# Charger.net
KiCad netlist of a schematic drawn in Altium Designer
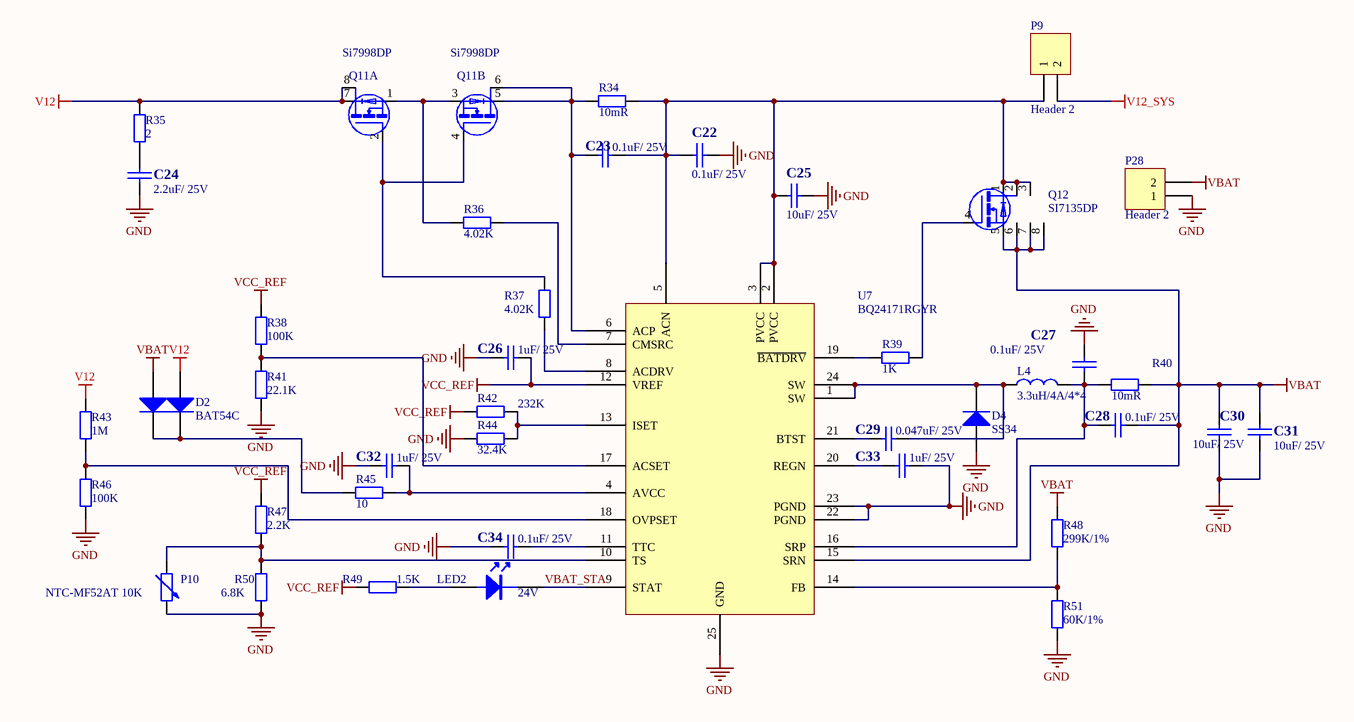
[diagram p0: Charger.SchDoc]

(export (version "E")
  (design (tool "Eeschema 10.0.6"))
  (components
    (comp (ref "C22")
      (value "0.1uF/ 25V")
      (footprint "0603C")
      (description "Capacitor")
      (libsource (lib "*") (part "CAP"))
    )
    (comp (ref "C23")
      (value "0.1uF/ 25V")
      (footprint "0603C")
      (description "Capacitor")
      (libsource (lib "*") (part "CAP"))
    )
    (comp (ref "C24")
      (value "2.2uF/ 25V")
      (footprint "0603C")
      (description "Capacitor")
      (libsource (lib "*") (part "CAP"))
    )
    (comp (ref "C25")
      (value "10uF/ 25V")
      (footprint "0603C")
      (description "Capacitor")
      (libsource (lib "*") (part "CAP"))
    )
    (comp (ref "C26")
      (value "1uF/ 25V")
      (footprint "0603C")
      (description "Capacitor")
      (libsource (lib "*") (part "CAP"))
    )
    (comp (ref "C27")
      (value "0.1uF/ 25V")
      (footprint "0603C")
      (description "Capacitor")
      (libsource (lib "*") (part "CAP"))
    )
    (comp (ref "C28")
      (value "0.1uF/ 25V")
      (footprint "0603C")
      (description "Capacitor")
      (libsource (lib "*") (part "CAP"))
    )
    (comp (ref "C29")
      (value "0.047uF/ 25V")
      (footprint "0603C")
      (description "Capacitor")
      (libsource (lib "*") (part "CAP"))
    )
    (comp (ref "C30")
      (value "10uF/ 25V")
      (footprint "0603C")
      (description "Capacitor")
      (libsource (lib "*") (part "CAP"))
    )
    (comp (ref "C31")
      (value "10uF/ 25V")
      (footprint "0603C")
      (description "Capacitor")
      (libsource (lib "*") (part "CAP"))
    )
    (comp (ref "C32")
      (value "1uF/ 25V")
      (footprint "0603C")
      (description "Capacitor")
      (libsource (lib "*") (part "CAP"))
    )
    (comp (ref "C33")
      (value "1uF/ 25V")
      (footprint "0603C")
      (description "Capacitor")
      (libsource (lib "*") (part "CAP"))
    )
    (comp (ref "C34")
      (value "0.1uF/ 25V")
      (footprint "0603C")
      (description "Capacitor")
      (libsource (lib "*") (part "CAP"))
    )
    (comp (ref "D2") (value "BAT54C") (footprint "SOT23-3") (libsource (lib "stm32") (part "BAT54C")))
    (comp (ref "D4") (value "SS34") (footprint "SMA") (libsource (lib "Sch_library") (part "DIODE")))
    (comp (ref "L4")
      (value "3.3uH/4A/4*4")
      (footprint "INDUCTOR_4X4X2")
      (libsource (lib "Sch_library") (part "IND"))
    )
    (comp (ref "LED2") (value "24V") (footprint "0603LED") (libsource (lib "*") (part "LED")))
    (comp (ref "P9")
      (value "Header 2")
      (footprint "HDR1X2")
      (description "Header, 2-Pin")
      (fields (field (name "PUBLISHER") "Altium Limited"))
      (libsource (lib "Miscellaneous Connectors") (part "Header 2"))
    )
    (comp (ref "P10")
      (value "NTC-MF52AT 10K")
      (footprint "SMD-0603")
      (description "卧贴")
      (libsource (lib "ABB") (part "RES3"))
    )
    (comp (ref "P28")
      (value "Header 2")
      (footprint "2X2.54MMW")
      (description "Header, 2-Pin")
      (fields (field (name "PUBLISHER") "Altium Limited"))
      (libsource (lib "") (part "Header 2_1"))
    )
    (comp (ref "Q11")
      (value "Si7998DP")
      (footprint "Si7998DP")
      (libsource (lib "Y0801_V14") (part "SI7940DP"))
    )
    (comp (ref "Q12")
      (value "SI7135DP")
      (footprint "PowerPAK SO-8")
      (libsource (lib "stm32") (part "SI7135DP"))
    )
    (comp (ref "R34")
      (value "10mR")
      (footprint "2512R")
      (description "贴片电阻 5%")
      (libsource (lib "XiaoyI") (part "RES2"))
    )
    (comp (ref "R35")
      (value "2")
      (footprint "SMD-0603")
      (description "贴片电阻 5%")
      (libsource (lib "") (part "RES2_2"))
    )
    (comp (ref "R36")
      (value "4.02K")
      (footprint "SMD-0603")
      (description "贴片电阻 5%")
      (libsource (lib "XiaoyI") (part "RES2"))
    )
    (comp (ref "R37")
      (value "4.02K")
      (footprint "SMD-0603")
      (description "贴片电阻 5%")
      (libsource (lib "") (part "RES2_2"))
    )
    (comp (ref "R38")
      (value "100K")
      (footprint "SMD-0603")
      (description "贴片电阻 5%")
      (libsource (lib "") (part "RES2_2"))
    )
    (comp (ref "R39")
      (value "1K")
      (footprint "0603R")
      (description "贴片电阻 5%")
      (libsource (lib "XiaoyI") (part "RES2"))
    )
    (comp (ref "R40")
      (value "10mR")
      (footprint "2512R")
      (description "贴片电阻 5%")
      (libsource (lib "XiaoyI") (part "RES2"))
    )
    (comp (ref "R41")
      (value "22.1K")
      (footprint "SMD-0603")
      (description "贴片电阻 5%")
      (libsource (lib "") (part "RES2_2"))
    )
    (comp (ref "R42")
      (value "232K")
      (footprint "SMD-0603")
      (description "贴片电阻 5%")
      (libsource (lib "XiaoyI") (part "RES2"))
    )
    (comp (ref "R43")
      (value "1M")
      (footprint "SMD-0603")
      (description "贴片电阻 5%")
      (libsource (lib "") (part "RES2_2"))
    )
    (comp (ref "R44")
      (value "32.4K")
      (footprint "SMD-0603")
      (description "贴片电阻 5%")
      (libsource (lib "XiaoyI") (part "RES2"))
    )
    (comp (ref "R45")
      (value "10")
      (footprint "SMD-0603")
      (description "贴片电阻 5%")
      (libsource (lib "XiaoyI") (part "RES2"))
    )
    (comp (ref "R46")
      (value "100K")
      (footprint "SMD-0603")
      (description "贴片电阻 5%")
      (libsource (lib "") (part "RES2_2"))
    )
    (comp (ref "R47")
      (value "2.2K")
      (footprint "SMD-0603")
      (description "贴片电阻 5%")
      (libsource (lib "") (part "RES2_2"))
    )
    (comp (ref "R48")
      (value "299K/1%")
      (footprint "SMD-0603")
      (description "贴片电阻 5%")
      (libsource (lib "") (part "RES2_1"))
    )
    (comp (ref "R49")
      (value "1.5K")
      (footprint "SMD-0603")
      (description "贴片电阻 5%")
      (libsource (lib "XiaoyI") (part "RES2"))
    )
    (comp (ref "R50")
      (value "6.8K")
      (footprint "SMD-0603")
      (description "贴片电阻 5%")
      (libsource (lib "") (part "RES2_2"))
    )
    (comp (ref "R51")
      (value "60K/1%")
      (footprint "SMD-0603")
      (description "贴片电阻 5%")
      (libsource (lib "") (part "RES2_1"))
    )
    (comp (ref "U7") (value "BQ24171RGYR") (footprint "bq24171") (libsource (lib "stm32") (part "bq24171")))
  )
  (nets
    (net (code "1") (name "/VBAT_STA") (class "Default")
      (node (ref "LED2") (pin "2") (pinfunction "2_2") (pintype "passive"))
      (node (ref "U7") (pin "9") (pinfunction "STAT_9") (pintype "passive"))
    )
    (net (code "2") (name "GND") (class "Default")
      (node (ref "C22") (pin "2") (pinfunction "2_2") (pintype "passive"))
      (node (ref "C24") (pin "2") (pinfunction "2_2") (pintype "passive"))
      (node (ref "C25") (pin "2") (pinfunction "2_2") (pintype "passive"))
      (node (ref "C26") (pin "2") (pinfunction "2_2") (pintype "passive"))
      (node (ref "C27") (pin "1") (pinfunction "1_1") (pintype "passive"))
      (node (ref "C30") (pin "2") (pinfunction "2_2") (pintype "passive"))
      (node (ref "C31") (pin "2") (pinfunction "2_2") (pintype "passive"))
      (node (ref "C32") (pin "2") (pinfunction "2_2") (pintype "passive"))
      (node (ref "C33") (pin "1") (pinfunction "1_1") (pintype "passive"))
      (node (ref "C34") (pin "2") (pinfunction "2_2") (pintype "passive"))
      (node (ref "D4") (pin "1") (pinfunction "A_1") (pintype "passive"))
      (node (ref "P10") (pin "2") (pinfunction "2_2") (pintype "passive"))
      (node (ref "P28") (pin "1") (pinfunction "1_1") (pintype "passive"))
      (node (ref "R41") (pin "1") (pinfunction "1_1") (pintype "passive"))
      (node (ref "R44") (pin "1") (pinfunction "1_1") (pintype "passive"))
      (node (ref "R46") (pin "1") (pinfunction "1_1") (pintype "passive"))
      (node (ref "R50") (pin "1") (pinfunction "1_1") (pintype "passive"))
      (node (ref "R51") (pin "2") (pinfunction "2_2") (pintype "passive"))
      (node (ref "U7") (pin "22") (pinfunction "PGND_22") (pintype "passive"))
      (node (ref "U7") (pin "23") (pinfunction "PGND_23") (pintype "passive"))
      (node (ref "U7") (pin "25") (pinfunction "GND_25") (pintype "passive"))
    )
    (net (code "3") (name "Net-(C24-Pad1)") (class "Default")
      (node (ref "C24") (pin "1") (pinfunction "1_1") (pintype "passive"))
      (node (ref "R35") (pin "1") (pinfunction "1_1") (pintype "passive"))
    )
    (net (code "4") (name "Net-(D2-K)") (class "Default")
      (node (ref "D2") (pin "3") (pinfunction "K_3") (pintype "passive"))
      (node (ref "R45") (pin "1") (pinfunction "1_1") (pintype "passive"))
    )
    (net (code "5") (name "Net-(D4-K)") (class "Default")
      (node (ref "C29") (pin "1") (pinfunction "1_1") (pintype "passive"))
      (node (ref "D4") (pin "2") (pinfunction "K_2") (pintype "passive"))
      (node (ref "L4") (pin "1") (pinfunction "1_1") (pintype "passive"))
      (node (ref "U7") (pin "1") (pinfunction "SW_1") (pintype "passive"))
      (node (ref "U7") (pin "24") (pinfunction "SW_24") (pintype "passive"))
    )
    (net (code "6") (name "Net-(LED2-Pad1)") (class "Default")
      (node (ref "LED2") (pin "1") (pinfunction "1_1") (pintype "passive"))
      (node (ref "R49") (pin "2") (pinfunction "2_2") (pintype "passive"))
    )
    (net (code "7") (name "Net-(Q11A-G1)") (class "Default")
      (node (ref "Q11") (pin "2") (pinfunction "G1_2") (pintype "passive"))
      (node (ref "Q11") (pin "4") (pinfunction "G2_4") (pintype "passive"))
      (node (ref "R37") (pin "2") (pinfunction "2_2") (pintype "passive"))
    )
    (net (code "8") (name "Net-(Q11A-S1)") (class "Default")
      (node (ref "Q11") (pin "1") (pinfunction "S1_1") (pintype "passive"))
      (node (ref "Q11") (pin "3") (pinfunction "S2_3") (pintype "passive"))
      (node (ref "R36") (pin "1") (pinfunction "1_1") (pintype "passive"))
    )
    (net (code "9") (name "Net-(Q12-G1)") (class "Default")
      (node (ref "Q12") (pin "4") (pinfunction "G1_4") (pintype "passive"))
      (node (ref "R39") (pin "2") (pinfunction "2_2") (pintype "passive"))
    )
    (net (code "10") (name "Net-(U7-ACDRV)") (class "Default")
      (node (ref "R37") (pin "1") (pinfunction "1_1") (pintype "passive"))
      (node (ref "U7") (pin "8") (pinfunction "ACDRV_8") (pintype "passive"))
    )
    (net (code "11") (name "Net-(U7-ACN)") (class "Default")
      (node (ref "C22") (pin "1") (pinfunction "1_1") (pintype "passive"))
      (node (ref "C23") (pin "2") (pinfunction "2_2") (pintype "passive"))
      (node (ref "C25") (pin "1") (pinfunction "1_1") (pintype "passive"))
      (node (ref "P9") (pin "1") (pinfunction "1_1") (pintype "passive"))
      (node (ref "Q12") (pin "1") (pinfunction "S_1") (pintype "passive"))
      (node (ref "Q12") (pin "2") (pinfunction "S_2") (pintype "passive"))
      (node (ref "Q12") (pin "3") (pinfunction "S_3") (pintype "passive"))
      (node (ref "R34") (pin "2") (pinfunction "2_2") (pintype "passive"))
      (node (ref "U7") (pin "2") (pinfunction "PVCC_2") (pintype "passive"))
      (node (ref "U7") (pin "3") (pinfunction "PVCC_3") (pintype "passive"))
      (node (ref "U7") (pin "5") (pinfunction "ACN_5") (pintype "passive"))
    )
    (net (code "12") (name "Net-(U7-ACP)") (class "Default")
      (node (ref "C23") (pin "1") (pinfunction "1_1") (pintype "passive"))
      (node (ref "Q11") (pin "5") (pinfunction "D2_5") (pintype "passive"))
      (node (ref "Q11") (pin "6") (pinfunction "D2_6") (pintype "passive"))
      (node (ref "R34") (pin "1") (pinfunction "1_1") (pintype "passive"))
      (node (ref "U7") (pin "6") (pinfunction "ACP_6") (pintype "passive"))
    )
    (net (code "13") (name "Net-(U7-ACSET)") (class "Default")
      (node (ref "R38") (pin "1") (pinfunction "1_1") (pintype "passive"))
      (node (ref "R41") (pin "2") (pinfunction "2_2") (pintype "passive"))
      (node (ref "U7") (pin "17") (pinfunction "ACSET_17") (pintype "passive"))
    )
    (net (code "14") (name "Net-(U7-AVCC)") (class "Default")
      (node (ref "C32") (pin "1") (pinfunction "1_1") (pintype "passive"))
      (node (ref "R45") (pin "2") (pinfunction "2_2") (pintype "passive"))
      (node (ref "U7") (pin "4") (pinfunction "AVCC_4") (pintype "passive"))
    )
    (net (code "15") (name "Net-(U7-BTST)") (class "Default")
      (node (ref "C29") (pin "2") (pinfunction "2_2") (pintype "passive"))
      (node (ref "U7") (pin "21") (pinfunction "BTST_21") (pintype "passive"))
    )
    (net (code "16") (name "Net-(U7-CMSRC)") (class "Default")
      (node (ref "R36") (pin "2") (pinfunction "2_2") (pintype "passive"))
      (node (ref "U7") (pin "7") (pinfunction "CMSRC_7") (pintype "passive"))
    )
    (net (code "17") (name "Net-(U7-FB)") (class "Default")
      (node (ref "R48") (pin "2") (pinfunction "2_2") (pintype "passive"))
      (node (ref "R51") (pin "1") (pinfunction "1_1") (pintype "passive"))
      (node (ref "U7") (pin "14") (pinfunction "FB_14") (pintype "passive"))
    )
    (net (code "18") (name "Net-(U7-ISET)") (class "Default")
      (node (ref "R42") (pin "2") (pinfunction "2_2") (pintype "passive"))
      (node (ref "R44") (pin "2") (pinfunction "2_2") (pintype "passive"))
      (node (ref "U7") (pin "13") (pinfunction "ISET_13") (pintype "passive"))
    )
    (net (code "19") (name "Net-(U7-OVPSET)") (class "Default")
      (node (ref "R43") (pin "1") (pinfunction "1_1") (pintype "passive"))
      (node (ref "R46") (pin "2") (pinfunction "2_2") (pintype "passive"))
      (node (ref "U7") (pin "18") (pinfunction "OVPSET_18") (pintype "passive"))
    )
    (net (code "20") (name "Net-(U7-REGN)") (class "Default")
      (node (ref "C33") (pin "2") (pinfunction "2_2") (pintype "passive"))
      (node (ref "U7") (pin "20") (pinfunction "REGN_20") (pintype "passive"))
    )
    (net (code "21") (name "Net-(U7-SRP)") (class "Default")
      (node (ref "C27") (pin "2") (pinfunction "2_2") (pintype "passive"))
      (node (ref "C28") (pin "2") (pinfunction "2_2") (pintype "passive"))
      (node (ref "L4") (pin "2") (pinfunction "2_2") (pintype "passive"))
      (node (ref "R40") (pin "1") (pinfunction "1_1") (pintype "passive"))
      (node (ref "U7") (pin "16") (pinfunction "SRP_16") (pintype "passive"))
    )
    (net (code "22") (name "Net-(U7-TS)") (class "Default")
      (node (ref "P10") (pin "1") (pinfunction "1_1") (pintype "passive"))
      (node (ref "R47") (pin "1") (pinfunction "1_1") (pintype "passive"))
      (node (ref "R50") (pin "2") (pinfunction "2_2") (pintype "passive"))
      (node (ref "U7") (pin "10") (pinfunction "TS_10") (pintype "passive"))
    )
    (net (code "23") (name "Net-(U7-TTC)") (class "Default")
      (node (ref "C34") (pin "1") (pinfunction "1_1") (pintype "passive"))
      (node (ref "U7") (pin "11") (pinfunction "TTC_11") (pintype "passive"))
    )
    (net (code "24") (name "Net-(U7-~{BATDRV})") (class "Default")
      (node (ref "R39") (pin "1") (pinfunction "1_1") (pintype "passive"))
      (node (ref "U7") (pin "19") (pinfunction "~{BATDRV}_19") (pintype "passive"))
    )
    (net (code "25") (name "V12") (class "Default")
      (node (ref "D2") (pin "1") (pinfunction "A_1") (pintype "passive"))
      (node (ref "Q11") (pin "7") (pinfunction "D1_7") (pintype "passive"))
      (node (ref "Q11") (pin "8") (pinfunction "D1_8") (pintype "passive"))
      (node (ref "R35") (pin "2") (pinfunction "2_2") (pintype "passive"))
      (node (ref "R43") (pin "2") (pinfunction "2_2") (pintype "passive"))
    )
    (net (code "26") (name "V12_SYS") (class "Default")
      (node (ref "P9") (pin "2") (pinfunction "2_2") (pintype "passive"))
    )
    (net (code "27") (name "VBAT") (class "Default")
      (node (ref "C28") (pin "1") (pinfunction "1_1") (pintype "passive"))
      (node (ref "C30") (pin "1") (pinfunction "1_1") (pintype "passive"))
      (node (ref "C31") (pin "1") (pinfunction "1_1") (pintype "passive"))
      (node (ref "D2") (pin "2") (pinfunction "A_2") (pintype "passive"))
      (node (ref "P28") (pin "2") (pinfunction "2_2") (pintype "passive"))
      (node (ref "Q12") (pin "5") (pinfunction "D_5") (pintype "passive"))
      (node (ref "Q12") (pin "6") (pinfunction "D_6") (pintype "passive"))
      (node (ref "Q12") (pin "7") (pinfunction "D_7") (pintype "passive"))
      (node (ref "Q12") (pin "8") (pinfunction "D_8") (pintype "passive"))
      (node (ref "R40") (pin "2") (pinfunction "2_2") (pintype "passive"))
      (node (ref "R48") (pin "1") (pinfunction "1_1") (pintype "passive"))
      (node (ref "U7") (pin "15") (pinfunction "SRN_15") (pintype "passive"))
    )
    (net (code "28") (name "VCC_REF") (class "Default")
      (node (ref "C26") (pin "1") (pinfunction "1_1") (pintype "passive"))
      (node (ref "R38") (pin "2") (pinfunction "2_2") (pintype "passive"))
      (node (ref "R42") (pin "1") (pinfunction "1_1") (pintype "passive"))
      (node (ref "R47") (pin "2") (pinfunction "2_2") (pintype "passive"))
      (node (ref "R49") (pin "1") (pinfunction "1_1") (pintype "passive"))
      (node (ref "U7") (pin "12") (pinfunction "VREF_12") (pintype "passive"))
    )
  )
)
